# generator.net
KiCad netlist of a schematic drawn in EAGLE
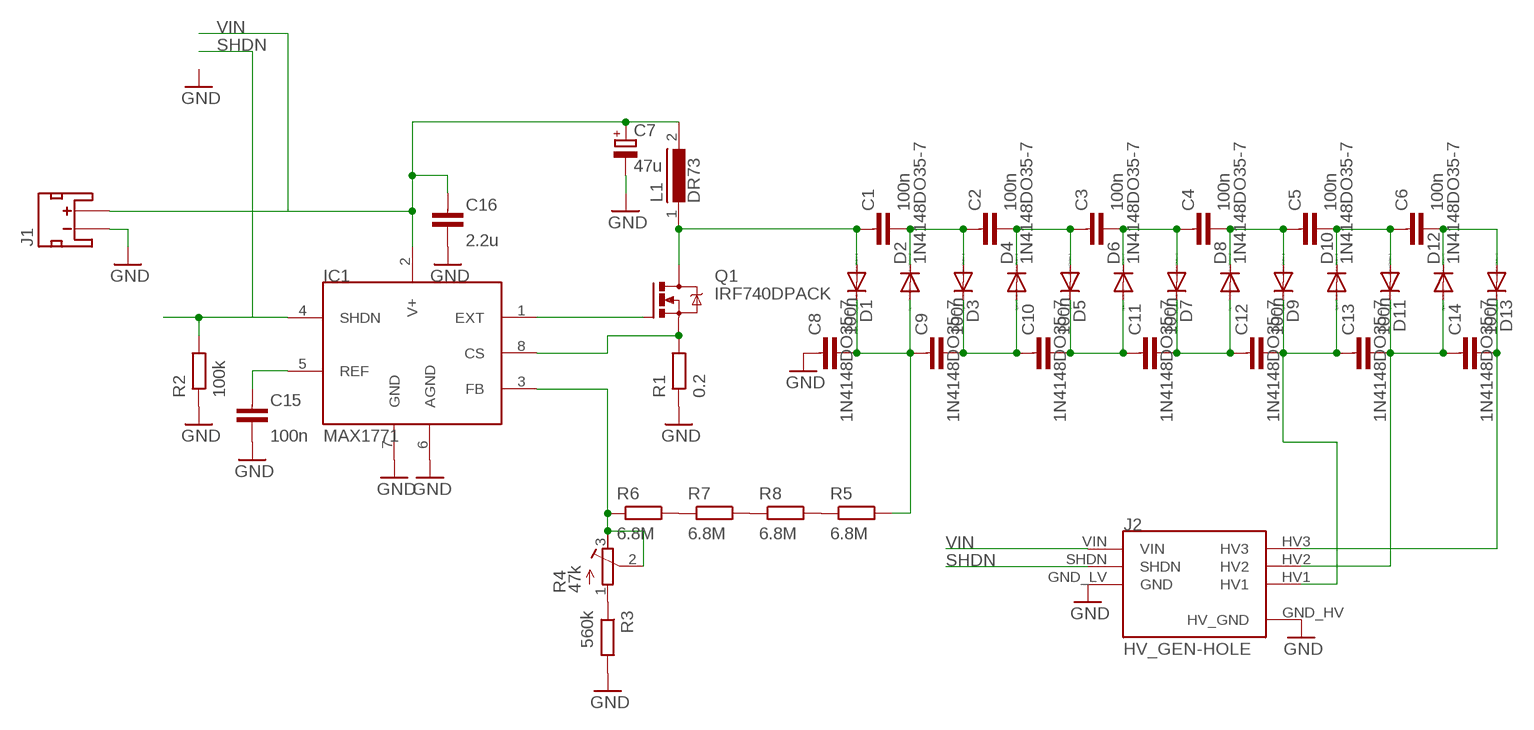
[diagram p0: schematic, sheet 1]

(export (version "E")
  (design (tool "Eeschema 10.0.6"))
  (components
    (comp (ref "C1")
      (value "100n")
      (footprint "eagle-import:C1206-N")
      (libsource (lib "eagle-import") (part "CAPACITOR1206-N"))
    )
    (comp (ref "C2")
      (value "100n")
      (footprint "eagle-import:C1206-N")
      (libsource (lib "eagle-import") (part "CAPACITOR1206-N"))
    )
    (comp (ref "C3")
      (value "100n")
      (footprint "eagle-import:C1206-N")
      (libsource (lib "eagle-import") (part "CAPACITOR1206-N"))
    )
    (comp (ref "C4")
      (value "100n")
      (footprint "eagle-import:C1206-N")
      (libsource (lib "eagle-import") (part "CAPACITOR1206-N"))
    )
    (comp (ref "C5")
      (value "100n")
      (footprint "eagle-import:C1206-N")
      (libsource (lib "eagle-import") (part "CAPACITOR1206-N"))
    )
    (comp (ref "C6")
      (value "100n")
      (footprint "eagle-import:C1206-N")
      (libsource (lib "eagle-import") (part "CAPACITOR1206-N"))
    )
    (comp (ref "C7")
      (value "47u")
      (footprint "eagle-import:E2-5")
      (fields (field (name "VOLTAGE") "16V"))
      (libsource (lib "eagle-import") (part "CPOL-EUE2-5"))
    )
    (comp (ref "C8")
      (value "100n")
      (footprint "eagle-import:C1206-N")
      (libsource (lib "eagle-import") (part "CAPACITOR1206-N"))
    )
    (comp (ref "C9")
      (value "100n")
      (footprint "eagle-import:C1206-N")
      (libsource (lib "eagle-import") (part "CAPACITOR1206-N"))
    )
    (comp (ref "C10")
      (value "100n")
      (footprint "eagle-import:C1206-N")
      (libsource (lib "eagle-import") (part "CAPACITOR1206-N"))
    )
    (comp (ref "C11")
      (value "100n")
      (footprint "eagle-import:C1206-N")
      (libsource (lib "eagle-import") (part "CAPACITOR1206-N"))
    )
    (comp (ref "C12")
      (value "100n")
      (footprint "eagle-import:C1206-N")
      (libsource (lib "eagle-import") (part "CAPACITOR1206-N"))
    )
    (comp (ref "C13")
      (value "100n")
      (footprint "eagle-import:C1206-N")
      (libsource (lib "eagle-import") (part "CAPACITOR1206-N"))
    )
    (comp (ref "C14")
      (value "100n")
      (footprint "eagle-import:C1206-N")
      (libsource (lib "eagle-import") (part "CAPACITOR1206-N"))
    )
    (comp (ref "C15")
      (value "100n")
      (footprint "eagle-import:C0603-N")
      (libsource (lib "eagle-import") (part "CAPACITOR0603-N"))
    )
    (comp (ref "C16")
      (value "2.2u")
      (footprint "eagle-import:C0603-N")
      (libsource (lib "eagle-import") (part "CAPACITOR0603-N"))
    )
    (comp (ref "D1")
      (value "1N4148DO35-7")
      (footprint "eagle-import:DO35-7")
      (libsource (lib "eagle-import") (part "1N4148DO35-7"))
    )
    (comp (ref "D2")
      (value "1N4148DO35-7")
      (footprint "eagle-import:DO35-7")
      (libsource (lib "eagle-import") (part "1N4148DO35-7"))
    )
    (comp (ref "D3")
      (value "1N4148DO35-7")
      (footprint "eagle-import:DO35-7")
      (libsource (lib "eagle-import") (part "1N4148DO35-7"))
    )
    (comp (ref "D4")
      (value "1N4148DO35-7")
      (footprint "eagle-import:DO35-7")
      (libsource (lib "eagle-import") (part "1N4148DO35-7"))
    )
    (comp (ref "D5")
      (value "1N4148DO35-7")
      (footprint "eagle-import:DO35-7")
      (libsource (lib "eagle-import") (part "1N4148DO35-7"))
    )
    (comp (ref "D6")
      (value "1N4148DO35-7")
      (footprint "eagle-import:DO35-7")
      (libsource (lib "eagle-import") (part "1N4148DO35-7"))
    )
    (comp (ref "D7")
      (value "1N4148DO35-7")
      (footprint "eagle-import:DO35-7")
      (libsource (lib "eagle-import") (part "1N4148DO35-7"))
    )
    (comp (ref "D8")
      (value "1N4148DO35-7")
      (footprint "eagle-import:DO35-7")
      (libsource (lib "eagle-import") (part "1N4148DO35-7"))
    )
    (comp (ref "D9")
      (value "1N4148DO35-7")
      (footprint "eagle-import:DO35-7")
      (libsource (lib "eagle-import") (part "1N4148DO35-7"))
    )
    (comp (ref "D10")
      (value "1N4148DO35-7")
      (footprint "eagle-import:DO35-7")
      (libsource (lib "eagle-import") (part "1N4148DO35-7"))
    )
    (comp (ref "D11")
      (value "1N4148DO35-7")
      (footprint "eagle-import:DO35-7")
      (libsource (lib "eagle-import") (part "1N4148DO35-7"))
    )
    (comp (ref "D12")
      (value "1N4148DO35-7")
      (footprint "eagle-import:DO35-7")
      (libsource (lib "eagle-import") (part "1N4148DO35-7"))
    )
    (comp (ref "D13")
      (value "1N4148DO35-7")
      (footprint "eagle-import:DO35-7")
      (libsource (lib "eagle-import") (part "1N4148DO35-7"))
    )
    (comp (ref "IC1")
      (value "MAX1771")
      (footprint "eagle-import:SO08")
      (libsource (lib "eagle-import") (part "MAX1771"))
    )
    (comp (ref "J1")
      (value "JST_2MM_MALE_TH")
      (footprint "eagle-import:JST-2-TH")
      (libsource (lib "eagle-import") (part "JST_2MM_MALE_TH"))
    )
    (comp (ref "J2")
      (value "HV_GEN-HOLE")
      (footprint "eagle-import:BRD-LAYOUT2")
      (libsource (lib "eagle-import") (part "HV_GEN-HOLE"))
    )
    (comp (ref "L1")
      (value "DR73")
      (footprint "eagle-import:DR73")
      (libsource (lib "eagle-import") (part "DR73"))
    )
    (comp (ref "Q1")
      (value "IRF740DPACK")
      (footprint "eagle-import:DPACK_1")
      (libsource (lib "eagle-import") (part "IRF740DPACK"))
    )
    (comp (ref "R1")
      (value "0.2")
      (footprint "eagle-import:R0805-N")
      (libsource (lib "eagle-import") (part "RESISTOR0805-N"))
    )
    (comp (ref "R2")
      (value "100k")
      (footprint "eagle-import:R0603-N")
      (libsource (lib "eagle-import") (part "RESISTOR0603-N"))
    )
    (comp (ref "R3")
      (value "560k")
      (footprint "eagle-import:R0603-N")
      (libsource (lib "eagle-import") (part "RESISTOR0603-N"))
    )
    (comp (ref "R4")
      (value "47k")
      (footprint "eagle-import:RTRIM3103")
      (libsource (lib "eagle-import") (part "R-TRIMM3103"))
    )
    (comp (ref "R5")
      (value "6.8M")
      (footprint "eagle-import:R0603-N")
      (libsource (lib "eagle-import") (part "RESISTOR0603-N"))
    )
    (comp (ref "R6")
      (value "6.8M")
      (footprint "eagle-import:R0603-N")
      (libsource (lib "eagle-import") (part "RESISTOR0603-N"))
    )
    (comp (ref "R7")
      (value "6.8M")
      (footprint "eagle-import:R0603-N")
      (libsource (lib "eagle-import") (part "RESISTOR0603-N"))
    )
    (comp (ref "R8")
      (value "6.8M")
      (footprint "eagle-import:R0603-N")
      (libsource (lib "eagle-import") (part "RESISTOR0603-N"))
    )
  )
  (nets
    (net (code "1") (name "/SHDN") (class "Default")
      (node (ref "IC1") (pin "4") (pinfunction "SHDN_4") (pintype "input"))
      (node (ref "J2") (pin "SHDN") (pinfunction "SHDN_SHDN") (pintype "bidirectional"))
      (node (ref "R2") (pin "2") (pinfunction "P$2_2") (pintype "passive"))
    )
    (net (code "2") (name "/VIN") (class "Default")
      (node (ref "C16") (pin "1") (pinfunction "1_1") (pintype "passive"))
      (node (ref "C7") (pin "+") (pinfunction "+_+") (pintype "passive"))
      (node (ref "IC1") (pin "2") (pinfunction "V+_2") (pintype "power_in"))
      (node (ref "J1") (pin "1") (pinfunction "+_1") (pintype "bidirectional"))
      (node (ref "J2") (pin "VIN") (pinfunction "VIN_VIN") (pintype "bidirectional"))
      (node (ref "L1") (pin "2") (pinfunction "2_2") (pintype "passive"))
    )
    (net (code "3") (name "GND") (class "Default")
      (node (ref "C15") (pin "2") (pinfunction "2_2") (pintype "passive"))
      (node (ref "C16") (pin "2") (pinfunction "2_2") (pintype "passive"))
      (node (ref "C7") (pin "-") (pinfunction "-_-") (pintype "passive"))
      (node (ref "C8") (pin "1") (pinfunction "1_1") (pintype "passive"))
      (node (ref "IC1") (pin "6") (pinfunction "AGND_6") (pintype "power_in"))
      (node (ref "IC1") (pin "7") (pinfunction "GND_7") (pintype "power_in"))
      (node (ref "J1") (pin "2") (pinfunction "-_2") (pintype "bidirectional"))
      (node (ref "J2") (pin "GND_HV") (pinfunction "HV_GND_GND_HV") (pintype "bidirectional"))
      (node (ref "J2") (pin "GND_LV") (pinfunction "GND_GND_LV") (pintype "bidirectional"))
      (node (ref "R1") (pin "1") (pinfunction "P$1_1") (pintype "passive"))
      (node (ref "R2") (pin "1") (pinfunction "P$1_1") (pintype "passive"))
      (node (ref "R3") (pin "2") (pinfunction "P$2_2") (pintype "passive"))
    )
    (net (code "4") (name "Net-(C1-Pad2)") (class "Default")
      (node (ref "C1") (pin "2") (pinfunction "2_2") (pintype "passive"))
      (node (ref "C2") (pin "1") (pinfunction "1_1") (pintype "passive"))
      (node (ref "D2") (pin "C") (pinfunction "C_C") (pintype "passive"))
      (node (ref "D3") (pin "A") (pinfunction "A_A") (pintype "passive"))
    )
    (net (code "5") (name "Net-(C2-Pad2)") (class "Default")
      (node (ref "C2") (pin "2") (pinfunction "2_2") (pintype "passive"))
      (node (ref "C3") (pin "1") (pinfunction "1_1") (pintype "passive"))
      (node (ref "D4") (pin "C") (pinfunction "C_C") (pintype "passive"))
      (node (ref "D5") (pin "A") (pinfunction "A_A") (pintype "passive"))
    )
    (net (code "6") (name "Net-(C3-Pad2)") (class "Default")
      (node (ref "C3") (pin "2") (pinfunction "2_2") (pintype "passive"))
      (node (ref "C4") (pin "1") (pinfunction "1_1") (pintype "passive"))
      (node (ref "D6") (pin "C") (pinfunction "C_C") (pintype "passive"))
      (node (ref "D7") (pin "A") (pinfunction "A_A") (pintype "passive"))
    )
    (net (code "7") (name "Net-(C4-Pad2)") (class "Default")
      (node (ref "C4") (pin "2") (pinfunction "2_2") (pintype "passive"))
      (node (ref "C5") (pin "1") (pinfunction "1_1") (pintype "passive"))
      (node (ref "D8") (pin "C") (pinfunction "C_C") (pintype "passive"))
      (node (ref "D9") (pin "A") (pinfunction "A_A") (pintype "passive"))
    )
    (net (code "8") (name "Net-(C5-Pad2)") (class "Default")
      (node (ref "C5") (pin "2") (pinfunction "2_2") (pintype "passive"))
      (node (ref "C6") (pin "1") (pinfunction "1_1") (pintype "passive"))
      (node (ref "D10") (pin "C") (pinfunction "C_C") (pintype "passive"))
      (node (ref "D11") (pin "A") (pinfunction "A_A") (pintype "passive"))
    )
    (net (code "9") (name "Net-(C6-Pad2)") (class "Default")
      (node (ref "C6") (pin "2") (pinfunction "2_2") (pintype "passive"))
      (node (ref "D12") (pin "C") (pinfunction "C_C") (pintype "passive"))
      (node (ref "D13") (pin "A") (pinfunction "A_A") (pintype "passive"))
    )
    (net (code "10") (name "Net-(C10-Pad1)") (class "Default")
      (node (ref "C10") (pin "1") (pinfunction "1_1") (pintype "passive"))
      (node (ref "C9") (pin "2") (pinfunction "2_2") (pintype "passive"))
      (node (ref "D3") (pin "C") (pinfunction "C_C") (pintype "passive"))
      (node (ref "D4") (pin "A") (pinfunction "A_A") (pintype "passive"))
    )
    (net (code "11") (name "Net-(C10-Pad2)") (class "Default")
      (node (ref "C10") (pin "2") (pinfunction "2_2") (pintype "passive"))
      (node (ref "C11") (pin "1") (pinfunction "1_1") (pintype "passive"))
      (node (ref "D5") (pin "C") (pinfunction "C_C") (pintype "passive"))
      (node (ref "D6") (pin "A") (pinfunction "A_A") (pintype "passive"))
    )
    (net (code "12") (name "Net-(C11-Pad2)") (class "Default")
      (node (ref "C11") (pin "2") (pinfunction "2_2") (pintype "passive"))
      (node (ref "C12") (pin "1") (pinfunction "1_1") (pintype "passive"))
      (node (ref "D7") (pin "C") (pinfunction "C_C") (pintype "passive"))
      (node (ref "D8") (pin "A") (pinfunction "A_A") (pintype "passive"))
    )
    (net (code "13") (name "Net-(C12-Pad2)") (class "Default")
      (node (ref "C12") (pin "2") (pinfunction "2_2") (pintype "passive"))
      (node (ref "C13") (pin "1") (pinfunction "1_1") (pintype "passive"))
      (node (ref "D10") (pin "A") (pinfunction "A_A") (pintype "passive"))
      (node (ref "D9") (pin "C") (pinfunction "C_C") (pintype "passive"))
      (node (ref "J2") (pin "HV1") (pinfunction "HV1_HV1") (pintype "bidirectional"))
    )
    (net (code "14") (name "Net-(C13-Pad2)") (class "Default")
      (node (ref "C13") (pin "2") (pinfunction "2_2") (pintype "passive"))
      (node (ref "C14") (pin "1") (pinfunction "1_1") (pintype "passive"))
      (node (ref "D11") (pin "C") (pinfunction "C_C") (pintype "passive"))
      (node (ref "D12") (pin "A") (pinfunction "A_A") (pintype "passive"))
      (node (ref "J2") (pin "HV2") (pinfunction "HV2_HV2") (pintype "bidirectional"))
    )
    (net (code "15") (name "Net-(C14-Pad2)") (class "Default")
      (node (ref "C14") (pin "2") (pinfunction "2_2") (pintype "passive"))
      (node (ref "D13") (pin "C") (pinfunction "C_C") (pintype "passive"))
      (node (ref "J2") (pin "HV3") (pinfunction "HV3_HV3") (pintype "bidirectional"))
    )
    (net (code "16") (name "Net-(IC1-CS)") (class "Default")
      (node (ref "IC1") (pin "8") (pinfunction "CS_8") (pintype "input"))
      (node (ref "Q1") (pin "E") (pinfunction "S_E") (pintype "passive"))
      (node (ref "R1") (pin "2") (pinfunction "P$2_2") (pintype "passive"))
    )
    (net (code "17") (name "Net-(IC1-EXT)") (class "Default")
      (node (ref "IC1") (pin "1") (pinfunction "EXT_1") (pintype "output"))
      (node (ref "Q1") (pin "B") (pinfunction "G_B") (pintype "passive"))
    )
    (net (code "18") (name "Net-(IC1-FB)") (class "Default")
      (node (ref "IC1") (pin "3") (pinfunction "FB_3") (pintype "input"))
      (node (ref "R4") (pin "2") (pinfunction "S_2") (pintype "passive"))
      (node (ref "R4") (pin "3") (pinfunction "E_3") (pintype "passive"))
      (node (ref "R6") (pin "1") (pinfunction "P$1_1") (pintype "passive"))
    )
    (net (code "19") (name "Net-(IC1-REF)") (class "Default")
      (node (ref "C15") (pin "1") (pinfunction "1_1") (pintype "passive"))
      (node (ref "IC1") (pin "5") (pinfunction "REF_5") (pintype "input"))
    )
    (net (code "20") (name "Net-(Q1-D)") (class "Default")
      (node (ref "C1") (pin "1") (pinfunction "1_1") (pintype "passive"))
      (node (ref "D1") (pin "A") (pinfunction "A_A") (pintype "passive"))
      (node (ref "L1") (pin "1") (pinfunction "1_1") (pintype "passive"))
      (node (ref "Q1") (pin "C") (pinfunction "D_C") (pintype "passive"))
    )
    (net (code "21") (name "Net-(R3-P$1)") (class "Default")
      (node (ref "R3") (pin "1") (pinfunction "P$1_1") (pintype "passive"))
      (node (ref "R4") (pin "1") (pinfunction "A_1") (pintype "passive"))
    )
    (net (code "22") (name "Net-(R5-P$1)") (class "Default")
      (node (ref "R5") (pin "1") (pinfunction "P$1_1") (pintype "passive"))
      (node (ref "R8") (pin "2") (pinfunction "P$2_2") (pintype "passive"))
    )
    (net (code "23") (name "Net-(R5-P$2)") (class "Default")
      (node (ref "C8") (pin "2") (pinfunction "2_2") (pintype "passive"))
      (node (ref "C9") (pin "1") (pinfunction "1_1") (pintype "passive"))
      (node (ref "D1") (pin "C") (pinfunction "C_C") (pintype "passive"))
      (node (ref "D2") (pin "A") (pinfunction "A_A") (pintype "passive"))
      (node (ref "R5") (pin "2") (pinfunction "P$2_2") (pintype "passive"))
    )
    (net (code "24") (name "Net-(R6-P$2)") (class "Default")
      (node (ref "R6") (pin "2") (pinfunction "P$2_2") (pintype "passive"))
      (node (ref "R7") (pin "1") (pinfunction "P$1_1") (pintype "passive"))
    )
    (net (code "25") (name "Net-(R7-P$2)") (class "Default")
      (node (ref "R7") (pin "2") (pinfunction "P$2_2") (pintype "passive"))
      (node (ref "R8") (pin "1") (pinfunction "P$1_1") (pintype "passive"))
    )
  )
)
